# ArduinoProMiniKame.net
KiCad netlist of a schematic drawn in EAGLE
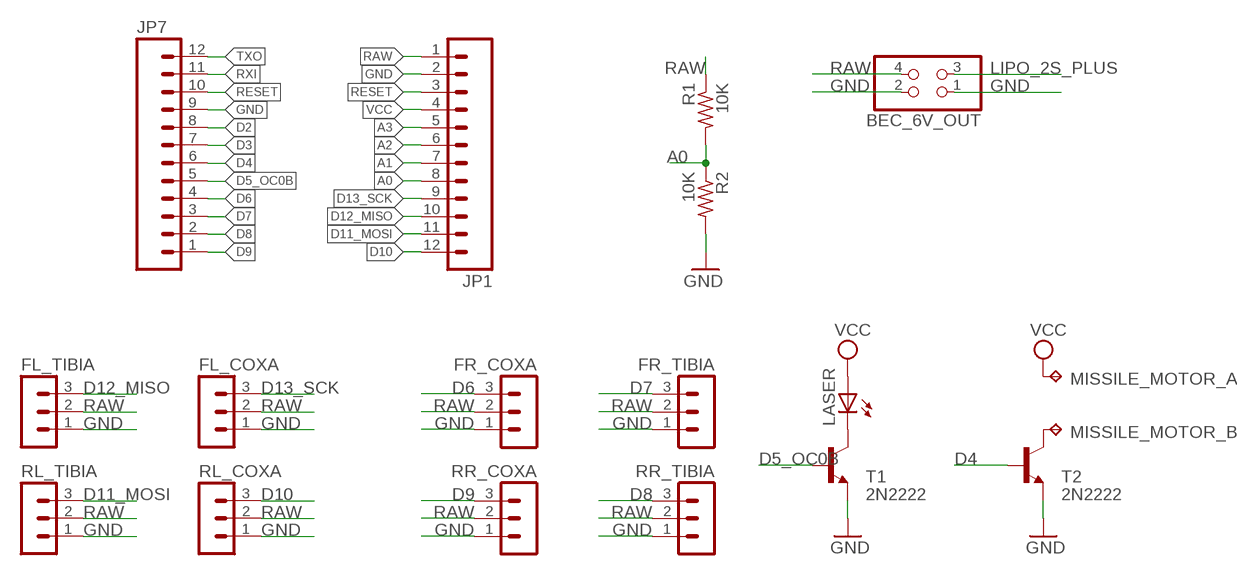
[diagram p0: schematic, sheet 1]

(export (version "E")
  (design (tool "Eeschema 10.0.6"))
  (components
    (comp (ref "BEC_6V_OUT")
      (value "PINHD-2X2")
      (footprint "eagle-import:2X02")
      (libsource (lib "eagle-import") (part "PINHD-2X2"))
    )
    (comp (ref "FL_COXA")
      (value "MA03-1")
      (footprint "eagle-import:MA03-1")
      (libsource (lib "eagle-import") (part "MA03-1"))
    )
    (comp (ref "FL_TIBIA")
      (value "MA03-1")
      (footprint "eagle-import:MA03-1")
      (libsource (lib "eagle-import") (part "MA03-1"))
    )
    (comp (ref "FR_COXA")
      (value "MA03-1")
      (footprint "eagle-import:MA03-1")
      (libsource (lib "eagle-import") (part "MA03-1"))
    )
    (comp (ref "FR_TIBIA")
      (value "MA03-1")
      (footprint "eagle-import:MA03-1")
      (libsource (lib "eagle-import") (part "MA03-1"))
    )
    (comp (ref "JP1")
      (value "M12PTH")
      (footprint "eagle-import:1X12")
      (libsource (lib "eagle-import") (part "M12PTH"))
    )
    (comp (ref "JP7")
      (value "M12PTH")
      (footprint "eagle-import:1X12")
      (libsource (lib "eagle-import") (part "M12PTH"))
    )
    (comp (ref "LASER")
      (value "LED")
      (footprint "eagle-import:SMARTLED-TTW")
      (libsource (lib "eagle-import") (part "LED"))
    )
    (comp (ref "MISSILE_MOTOR_")
      (value "TP2P2-38-20")
      (footprint "eagle-import:P2-38-20")
      (libsource (lib "eagle-import") (part "TP2P2-38-20"))
    )
    (comp (ref "R1")
      (value "10K")
      (footprint "eagle-import:R2010")
      (libsource (lib "eagle-import") (part "R-US_R2010"))
    )
    (comp (ref "R2")
      (value "10K")
      (footprint "eagle-import:R2010")
      (libsource (lib "eagle-import") (part "R-US_R2010"))
    )
    (comp (ref "RL_COXA")
      (value "MA03-1")
      (footprint "eagle-import:MA03-1")
      (libsource (lib "eagle-import") (part "MA03-1"))
    )
    (comp (ref "RL_TIBIA")
      (value "MA03-1")
      (footprint "eagle-import:MA03-1")
      (libsource (lib "eagle-import") (part "MA03-1"))
    )
    (comp (ref "RR_COXA")
      (value "MA03-1")
      (footprint "eagle-import:MA03-1")
      (libsource (lib "eagle-import") (part "MA03-1"))
    )
    (comp (ref "RR_TIBIA")
      (value "MA03-1")
      (footprint "eagle-import:MA03-1")
      (libsource (lib "eagle-import") (part "MA03-1"))
    )
    (comp (ref "T1")
      (value "2N2222")
      (footprint "eagle-import:TO18")
      (libsource (lib "eagle-import") (part "2N2222"))
    )
    (comp (ref "T2")
      (value "2N2222")
      (footprint "eagle-import:TO18")
      (libsource (lib "eagle-import") (part "2N2222"))
    )
  )
  (nets
    (net (code "1") (name "/LIPO_2S_PLUS") (class "Default")
      (node (ref "BEC_6V_OUT") (pin "3") (pinfunction "3_3") (pintype "passive"))
    )
    (net (code "2") (name "A0") (class "Default")
      (node (ref "JP1") (pin "8") (pinfunction "8_8") (pintype "passive"))
      (node (ref "R1") (pin "2") (pinfunction "2_2") (pintype "passive"))
      (node (ref "R2") (pin "1") (pinfunction "1_1") (pintype "passive"))
    )
    (net (code "3") (name "A1") (class "Default")
      (node (ref "JP1") (pin "7") (pinfunction "7_7") (pintype "passive"))
    )
    (net (code "4") (name "A2") (class "Default")
      (node (ref "JP1") (pin "6") (pinfunction "6_6") (pintype "passive"))
    )
    (net (code "5") (name "A3") (class "Default")
      (node (ref "JP1") (pin "5") (pinfunction "5_5") (pintype "passive"))
    )
    (net (code "6") (name "D2") (class "Default")
      (node (ref "JP7") (pin "8") (pinfunction "8_8") (pintype "passive"))
    )
    (net (code "7") (name "D3") (class "Default")
      (node (ref "JP7") (pin "7") (pinfunction "7_7") (pintype "passive"))
    )
    (net (code "8") (name "D4") (class "Default")
      (node (ref "JP7") (pin "6") (pinfunction "6_6") (pintype "passive"))
      (node (ref "T2") (pin "2") (pinfunction "B_2") (pintype "passive"))
    )
    (net (code "9") (name "D5_OC0B") (class "Default")
      (node (ref "JP7") (pin "5") (pinfunction "5_5") (pintype "passive"))
      (node (ref "T1") (pin "2") (pinfunction "B_2") (pintype "passive"))
    )
    (net (code "10") (name "D6") (class "Default")
      (node (ref "FR_COXA") (pin "3") (pinfunction "3_3") (pintype "passive"))
      (node (ref "JP7") (pin "4") (pinfunction "4_4") (pintype "passive"))
    )
    (net (code "11") (name "D7") (class "Default")
      (node (ref "FR_TIBIA") (pin "3") (pinfunction "3_3") (pintype "passive"))
      (node (ref "JP7") (pin "3") (pinfunction "3_3") (pintype "passive"))
    )
    (net (code "12") (name "D8") (class "Default")
      (node (ref "JP7") (pin "2") (pinfunction "2_2") (pintype "passive"))
      (node (ref "RR_TIBIA") (pin "3") (pinfunction "3_3") (pintype "passive"))
    )
    (net (code "13") (name "D9") (class "Default")
      (node (ref "JP7") (pin "1") (pinfunction "1_1") (pintype "passive"))
      (node (ref "RR_COXA") (pin "3") (pinfunction "3_3") (pintype "passive"))
    )
    (net (code "14") (name "D10") (class "Default")
      (node (ref "JP1") (pin "12") (pinfunction "12_12") (pintype "passive"))
      (node (ref "RL_COXA") (pin "3") (pinfunction "3_3") (pintype "passive"))
    )
    (net (code "15") (name "D11_MOSI") (class "Default")
      (node (ref "JP1") (pin "11") (pinfunction "11_11") (pintype "passive"))
      (node (ref "RL_TIBIA") (pin "3") (pinfunction "3_3") (pintype "passive"))
    )
    (net (code "16") (name "D12_MISO") (class "Default")
      (node (ref "FL_TIBIA") (pin "3") (pinfunction "3_3") (pintype "passive"))
      (node (ref "JP1") (pin "10") (pinfunction "10_10") (pintype "passive"))
    )
    (net (code "17") (name "D13_SCK") (class "Default")
      (node (ref "FL_COXA") (pin "3") (pinfunction "3_3") (pintype "passive"))
      (node (ref "JP1") (pin "9") (pinfunction "9_9") (pintype "passive"))
    )
    (net (code "18") (name "GND") (class "Default")
      (node (ref "BEC_6V_OUT") (pin "1") (pinfunction "1_1") (pintype "passive"))
      (node (ref "BEC_6V_OUT") (pin "2") (pinfunction "2_2") (pintype "passive"))
      (node (ref "FL_COXA") (pin "1") (pinfunction "1_1") (pintype "passive"))
      (node (ref "FL_TIBIA") (pin "1") (pinfunction "1_1") (pintype "passive"))
      (node (ref "FR_COXA") (pin "1") (pinfunction "1_1") (pintype "passive"))
      (node (ref "FR_TIBIA") (pin "1") (pinfunction "1_1") (pintype "passive"))
      (node (ref "JP1") (pin "2") (pinfunction "2_2") (pintype "passive"))
      (node (ref "JP7") (pin "9") (pinfunction "9_9") (pintype "passive"))
      (node (ref "R2") (pin "2") (pinfunction "2_2") (pintype "passive"))
      (node (ref "RL_COXA") (pin "1") (pinfunction "1_1") (pintype "passive"))
      (node (ref "RL_TIBIA") (pin "1") (pinfunction "1_1") (pintype "passive"))
      (node (ref "RR_COXA") (pin "1") (pinfunction "1_1") (pintype "passive"))
      (node (ref "RR_TIBIA") (pin "1") (pinfunction "1_1") (pintype "passive"))
      (node (ref "T1") (pin "1") (pinfunction "E_1") (pintype "passive"))
      (node (ref "T2") (pin "1") (pinfunction "E_1") (pintype "passive"))
    )
    (net (code "19") (name "Net-(LASER-C)") (class "Default")
      (node (ref "LASER") (pin "C@1") (pinfunction "C_C@1") (pintype "passive"))
      (node (ref "T1") (pin "3") (pinfunction "C_3") (pintype "passive"))
    )
    (net (code "20") (name "Net-(MISSILE_MOTOR_B-TP)") (class "Default")
      (node (ref "MISSILE_MOTOR_") (pin "TP-2") (pinfunction "TP_TP-2") (pintype "input"))
      (node (ref "T2") (pin "3") (pinfunction "C_3") (pintype "passive"))
    )
    (net (code "21") (name "RAW") (class "Default")
      (node (ref "BEC_6V_OUT") (pin "4") (pinfunction "4_4") (pintype "passive"))
      (node (ref "FL_COXA") (pin "2") (pinfunction "2_2") (pintype "passive"))
      (node (ref "FL_TIBIA") (pin "2") (pinfunction "2_2") (pintype "passive"))
      (node (ref "FR_COXA") (pin "2") (pinfunction "2_2") (pintype "passive"))
      (node (ref "FR_TIBIA") (pin "2") (pinfunction "2_2") (pintype "passive"))
      (node (ref "JP1") (pin "1") (pinfunction "1_1") (pintype "passive"))
      (node (ref "R1") (pin "1") (pinfunction "1_1") (pintype "passive"))
      (node (ref "RL_COXA") (pin "2") (pinfunction "2_2") (pintype "passive"))
      (node (ref "RL_TIBIA") (pin "2") (pinfunction "2_2") (pintype "passive"))
      (node (ref "RR_COXA") (pin "2") (pinfunction "2_2") (pintype "passive"))
      (node (ref "RR_TIBIA") (pin "2") (pinfunction "2_2") (pintype "passive"))
    )
    (net (code "22") (name "RESET") (class "Default")
      (node (ref "JP1") (pin "3") (pinfunction "3_3") (pintype "passive"))
      (node (ref "JP7") (pin "10") (pinfunction "10_10") (pintype "passive"))
    )
    (net (code "23") (name "RXI") (class "Default")
      (node (ref "JP7") (pin "11") (pinfunction "11_11") (pintype "passive"))
    )
    (net (code "24") (name "TXO") (class "Default")
      (node (ref "JP7") (pin "12") (pinfunction "12_12") (pintype "passive"))
    )
    (net (code "25") (name "VCC") (class "Default")
      (node (ref "JP1") (pin "4") (pinfunction "4_4") (pintype "passive"))
      (node (ref "LASER") (pin "A@1") (pinfunction "A_A@1") (pintype "passive"))
      (node (ref "MISSILE_MOTOR_") (pin "TP-1") (pinfunction "TP_TP-1") (pintype "input"))
    )
  )
)
